# SparkFun_tDof-TMF8821.net
KiCad netlist of a schematic drawn in EAGLE
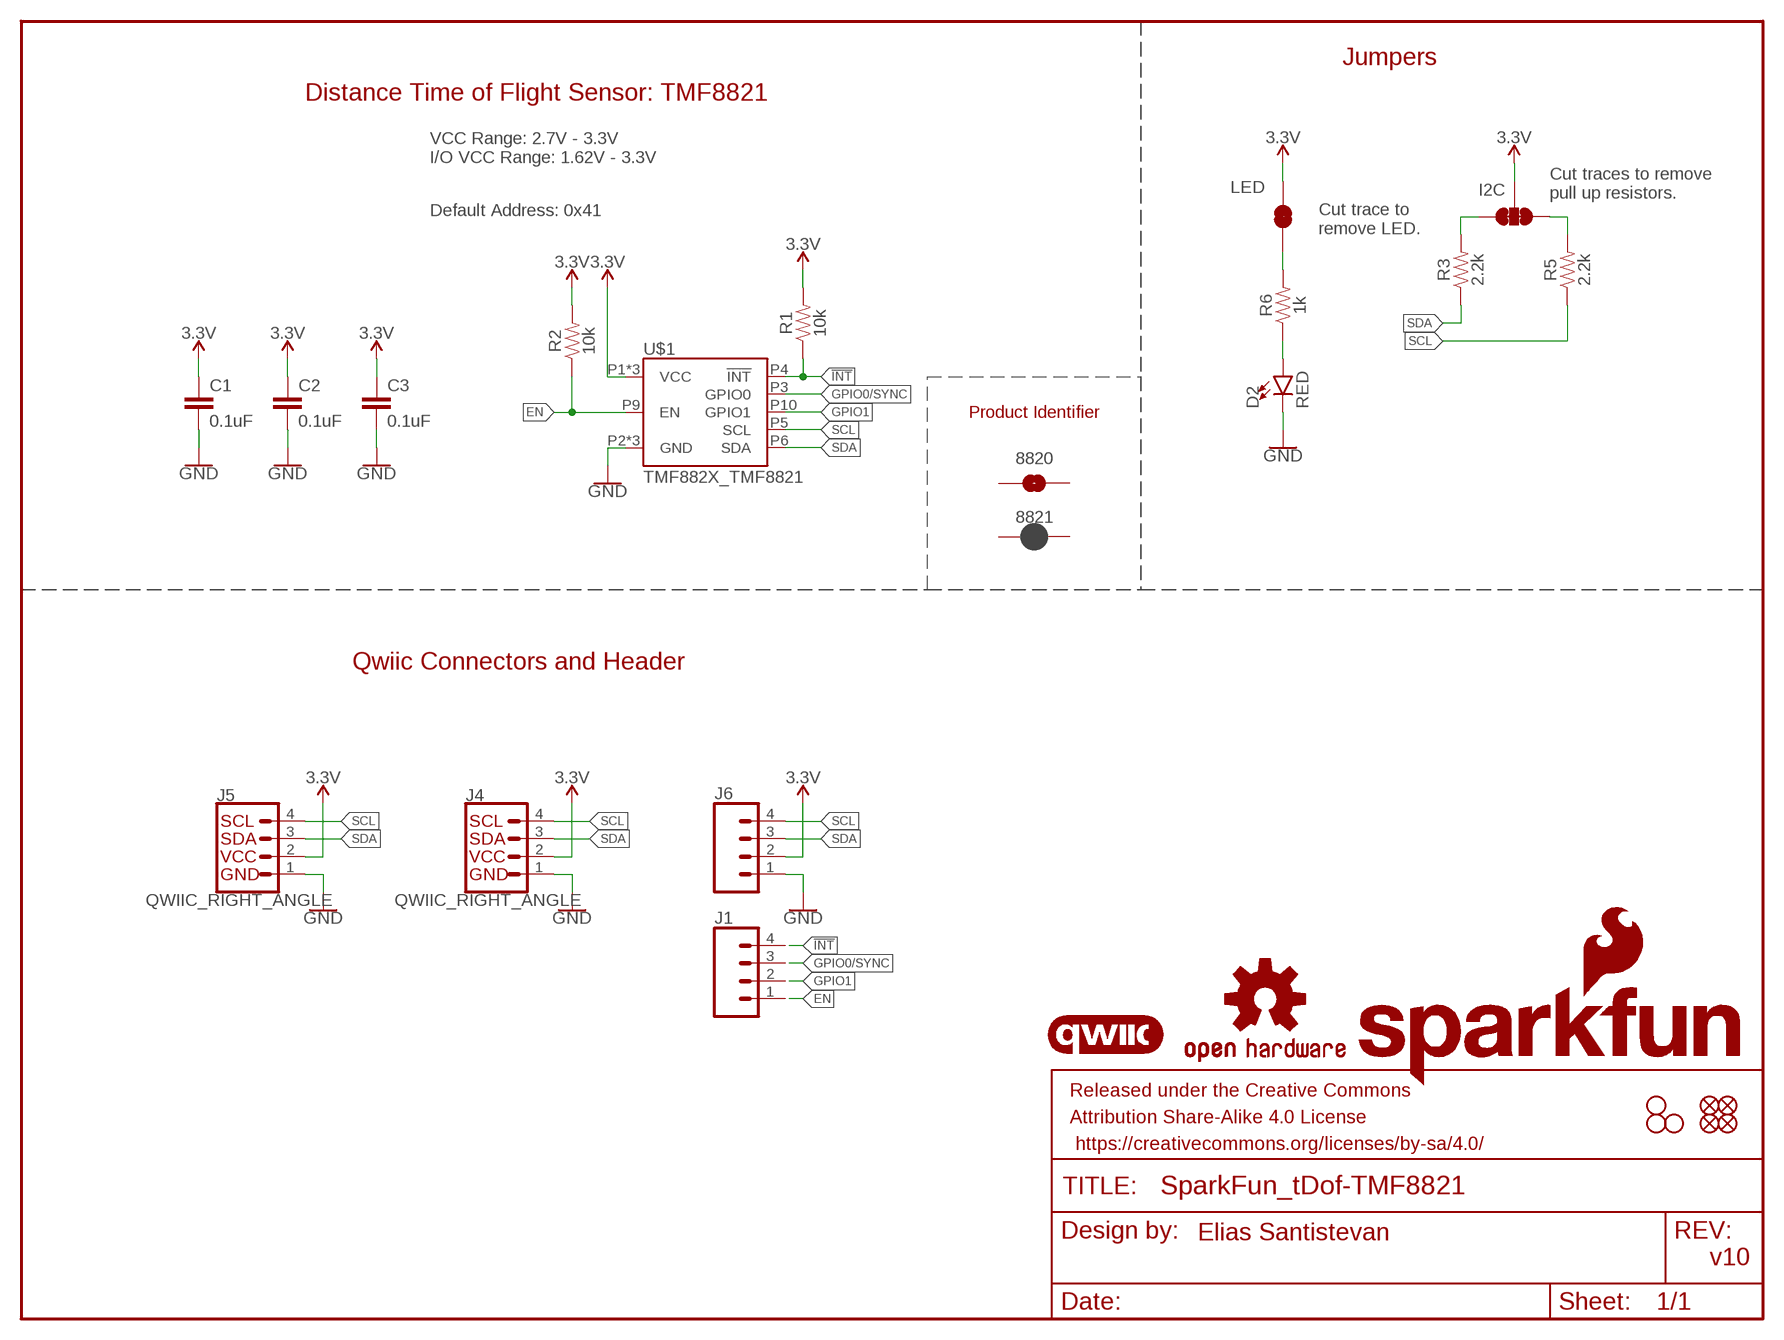
[diagram p0: schematic, sheet 1]

(export (version "E")
  (design (tool "Eeschema 10.0.6"))
  (components
    (comp (ref "8820")
      (value "JUMPER-SMT_2_NO_SILK")
      (footprint "eagle-import:SMT-JUMPER_2_NO_SILK")
      (libsource (lib "eagle-import") (part "JUMPER-SMT_2_NO_SILK"))
    )
    (comp (ref "8821")
      (value "JUMPER-SMT_2_NC_PASTE_SILK")
      (footprint "eagle-import:SMT-JUMPER_2_NC_PASTE_SILK")
      (libsource (lib "eagle-import") (part "JUMPER-SMT_2_NC_PASTE_SILK"))
    )
    (comp (ref "C1")
      (value "0.1uF")
      (footprint "eagle-import:0402-TIGHT")
      (libsource (lib "eagle-import") (part "0.1UF-0402T-6.3V-10%-X7R"))
    )
    (comp (ref "C2")
      (value "0.1uF")
      (footprint "eagle-import:0402-TIGHT")
      (libsource (lib "eagle-import") (part "0.1UF-0402T-6.3V-10%-X7R"))
    )
    (comp (ref "C3")
      (value "0.1uF")
      (footprint "eagle-import:0402-TIGHT")
      (libsource (lib "eagle-import") (part "0.1UF-0402T-6.3V-10%-X7R"))
    )
    (comp (ref "D2")
      (value "RED")
      (footprint "eagle-import:LED-0603")
      (libsource (lib "eagle-import") (part "LED-RED0603"))
    )
    (comp (ref "FD5")
      (value "FIDUCIALUFIDUCIAL")
      (footprint "eagle-import:FIDUCIAL-MICRO")
      (libsource (lib "eagle-import") (part "FIDUCIALUFIDUCIAL"))
    )
    (comp (ref "FD6")
      (value "FIDUCIALUFIDUCIAL")
      (footprint "eagle-import:FIDUCIAL-MICRO")
      (libsource (lib "eagle-import") (part "FIDUCIALUFIDUCIAL"))
    )
    (comp (ref "FD7")
      (value "FIDUCIALUFIDUCIAL")
      (footprint "eagle-import:FIDUCIAL-MICRO")
      (libsource (lib "eagle-import") (part "FIDUCIALUFIDUCIAL"))
    )
    (comp (ref "FD8")
      (value "FIDUCIALUFIDUCIAL")
      (footprint "eagle-import:FIDUCIAL-MICRO")
      (libsource (lib "eagle-import") (part "FIDUCIALUFIDUCIAL"))
    )
    (comp (ref "FRAME2")
      (value "FRAME-LETTER")
      (footprint "eagle-import:CREATIVE_COMMONS")
      (libsource (lib "eagle-import") (part "FRAME-LETTER"))
    )
    (comp (ref "H5")
      (value "STAND-OFFTIGHT")
      (footprint "eagle-import:STAND-OFF-TIGHT")
      (libsource (lib "eagle-import") (part "STAND-OFFTIGHT"))
    )
    (comp (ref "H6")
      (value "STAND-OFFTIGHT")
      (footprint "eagle-import:STAND-OFF-TIGHT")
      (libsource (lib "eagle-import") (part "STAND-OFFTIGHT"))
    )
    (comp (ref "H8")
      (value "STAND-OFFTIGHT")
      (footprint "eagle-import:STAND-OFF-TIGHT")
      (libsource (lib "eagle-import") (part "STAND-OFFTIGHT"))
    )
    (comp (ref "I2C")
      (value "I2C_PU")
      (footprint "eagle-import:SMT-JUMPER_3_2-NC_TRACE_SILK")
      (libsource (lib "eagle-import") (part "JUMPER-SMT_3_2-NC_TRACE_SILK"))
    )
    (comp (ref "J1")
      (value "CONN_041X04_NO_SILK_NO_POP")
      (footprint "eagle-import:1X04_NO_SILK")
      (libsource (lib "eagle-import") (part "CONN_041X04_NO_SILK_NO_POP"))
    )
    (comp (ref "J4")
      (value "QWIIC_RIGHT_ANGLE")
      (footprint "eagle-import:JST04_1MM_RA")
      (libsource (lib "eagle-import") (part "QWIIC_CONNECTORJS-1MM"))
    )
    (comp (ref "J5")
      (value "QWIIC_RIGHT_ANGLE")
      (footprint "eagle-import:JST04_1MM_RA")
      (libsource (lib "eagle-import") (part "QWIIC_CONNECTORJS-1MM"))
    )
    (comp (ref "J6")
      (value "CONN_041X04_NO_SILK")
      (footprint "eagle-import:1X04_NO_SILK")
      (libsource (lib "eagle-import") (part "CONN_041X04_NO_SILK"))
    )
    (comp (ref "LED")
      (value "LED")
      (footprint "eagle-import:SMT-JUMPER_2_NC_TRACE_SILK")
      (libsource (lib "eagle-import") (part "JUMPER-SMT_2_NC_TRACE_SILK"))
    )
    (comp (ref "LOGO3")
      (value "SFE_LOGO_NAME_FLAME.1_INCH")
      (footprint "eagle-import:SFE_LOGO_NAME_FLAME_.1")
      (libsource (lib "eagle-import") (part "SFE_LOGO_NAME_FLAME.1_INCH"))
    )
    (comp (ref "LOGO4")
      (value "OSHW-LOGOS")
      (footprint "eagle-import:OSHW-LOGO-S")
      (libsource (lib "eagle-import") (part "OSHW-LOGOS"))
    )
    (comp (ref "R1")
      (value "10k")
      (footprint "eagle-import:0603")
      (libsource (lib "eagle-import") (part "10KOHM-0603-1/10W-1%"))
    )
    (comp (ref "R2")
      (value "10k")
      (footprint "eagle-import:0603")
      (libsource (lib "eagle-import") (part "10KOHM-0603-1/10W-1%"))
    )
    (comp (ref "R3")
      (value "2.2k")
      (footprint "eagle-import:0603")
      (libsource (lib "eagle-import") (part "2.2KOHM-0603-1/10W-1%"))
    )
    (comp (ref "R5")
      (value "2.2k")
      (footprint "eagle-import:0603")
      (libsource (lib "eagle-import") (part "2.2KOHM-0603-1/10W-1%"))
    )
    (comp (ref "R6")
      (value "1k")
      (footprint "eagle-import:0603")
      (libsource (lib "eagle-import") (part "1KOHM-0603-1/10W-1%"))
    )
    (comp (ref "U$1")
      (value "TMF882X_TMF8821")
      (footprint "eagle-import:TMF882X")
      (libsource (lib "eagle-import") (part "TMF882X_TMF8821"))
    )
    (comp (ref "U$6")
      (value "QWIIC_LOGO_5MM")
      (footprint "eagle-import:QWIIC_5MM")
      (libsource (lib "eagle-import") (part "QWIIC_LOGO_5MM"))
    )
  )
  (nets
    (net (code "1") (name "/~{INT}") (class "Default")
      (node (ref "J1") (pin "4") (pinfunction "4_4") (pintype "passive"))
      (node (ref "R1") (pin "1") (pinfunction "1_1") (pintype "passive"))
      (node (ref "U$1") (pin "P4") (pinfunction "~{INT}_P4") (pintype "bidirectional"))
    )
    (net (code "2") (name "3.3V") (class "Default")
      (node (ref "C1") (pin "1") (pinfunction "1_1") (pintype "passive"))
      (node (ref "C2") (pin "1") (pinfunction "1_1") (pintype "passive"))
      (node (ref "C3") (pin "1") (pinfunction "1_1") (pintype "passive"))
      (node (ref "I2C") (pin "2") (pinfunction "2_2") (pintype "passive"))
      (node (ref "J4") (pin "2") (pinfunction "2_2") (pintype "power_in"))
      (node (ref "J5") (pin "2") (pinfunction "2_2") (pintype "power_in"))
      (node (ref "J6") (pin "2") (pinfunction "2_2") (pintype "passive"))
      (node (ref "LED") (pin "2") (pinfunction "2_2") (pintype "passive"))
      (node (ref "R1") (pin "2") (pinfunction "2_2") (pintype "passive"))
      (node (ref "R2") (pin "2") (pinfunction "2_2") (pintype "passive"))
      (node (ref "U$1") (pin "P1") (pinfunction "VCC_P1") (pintype "power_in"))
      (node (ref "U$1") (pin "P12") (pinfunction "VCC_P12") (pintype "power_in"))
      (node (ref "U$1") (pin "P7") (pinfunction "VCC_P7") (pintype "power_in"))
    )
    (net (code "3") (name "EN") (class "Default")
      (node (ref "J1") (pin "1") (pinfunction "1_1") (pintype "passive"))
      (node (ref "R2") (pin "1") (pinfunction "1_1") (pintype "passive"))
      (node (ref "U$1") (pin "P9") (pinfunction "EN_P9") (pintype "input"))
    )
    (net (code "4") (name "GND") (class "Default")
      (node (ref "C1") (pin "2") (pinfunction "2_2") (pintype "passive"))
      (node (ref "C2") (pin "2") (pinfunction "2_2") (pintype "passive"))
      (node (ref "C3") (pin "2") (pinfunction "2_2") (pintype "passive"))
      (node (ref "D2") (pin "C") (pinfunction "C_C") (pintype "passive"))
      (node (ref "J4") (pin "1") (pinfunction "1_1") (pintype "power_in"))
      (node (ref "J5") (pin "1") (pinfunction "1_1") (pintype "power_in"))
      (node (ref "J6") (pin "1") (pinfunction "1_1") (pintype "passive"))
      (node (ref "U$1") (pin "P11") (pinfunction "GND_P11") (pintype "power_in"))
      (node (ref "U$1") (pin "P2") (pinfunction "GND_P2") (pintype "power_in"))
      (node (ref "U$1") (pin "P8") (pinfunction "GND_P8") (pintype "power_in"))
    )
    (net (code "5") (name "GPIO0{slash}SYNC") (class "Default")
      (node (ref "J1") (pin "3") (pinfunction "3_3") (pintype "passive"))
      (node (ref "U$1") (pin "P3") (pinfunction "GPIO0_P3") (pintype "bidirectional"))
    )
    (net (code "6") (name "GPIO1") (class "Default")
      (node (ref "J1") (pin "2") (pinfunction "2_2") (pintype "passive"))
      (node (ref "U$1") (pin "P10") (pinfunction "GPIO1_P10") (pintype "bidirectional"))
    )
    (net (code "7") (name "Net-(D2-PadA)") (class "Default")
      (node (ref "D2") (pin "A") (pinfunction "A_A") (pintype "passive"))
      (node (ref "R6") (pin "1") (pinfunction "1_1") (pintype "passive"))
    )
    (net (code "8") (name "Net-(I2C-Pad1)") (class "Default")
      (node (ref "I2C") (pin "1") (pinfunction "1_1") (pintype "passive"))
      (node (ref "R5") (pin "2") (pinfunction "2_2") (pintype "passive"))
    )
    (net (code "9") (name "Net-(I2C-Pad3)") (class "Default")
      (node (ref "I2C") (pin "3") (pinfunction "3_3") (pintype "passive"))
      (node (ref "R3") (pin "2") (pinfunction "2_2") (pintype "passive"))
    )
    (net (code "10") (name "Net-(LED-Pad1)") (class "Default")
      (node (ref "LED") (pin "1") (pinfunction "1_1") (pintype "passive"))
      (node (ref "R6") (pin "2") (pinfunction "2_2") (pintype "passive"))
    )
    (net (code "11") (name "SCL") (class "Default")
      (node (ref "J4") (pin "4") (pinfunction "4_4") (pintype "passive"))
      (node (ref "J5") (pin "4") (pinfunction "4_4") (pintype "passive"))
      (node (ref "J6") (pin "4") (pinfunction "4_4") (pintype "passive"))
      (node (ref "R5") (pin "1") (pinfunction "1_1") (pintype "passive"))
      (node (ref "U$1") (pin "P5") (pinfunction "SCL_P5") (pintype "bidirectional"))
    )
    (net (code "12") (name "SDA") (class "Default")
      (node (ref "J4") (pin "3") (pinfunction "3_3") (pintype "passive"))
      (node (ref "J5") (pin "3") (pinfunction "3_3") (pintype "passive"))
      (node (ref "J6") (pin "3") (pinfunction "3_3") (pintype "passive"))
      (node (ref "R3") (pin "1") (pinfunction "1_1") (pintype "passive"))
      (node (ref "U$1") (pin "P6") (pinfunction "SDA_P6") (pintype "bidirectional"))
    )
    (net (code "13") (name "unconnected-(8820-Pad1)") (class "Default")
      (node (ref "8820") (pin "1") (pinfunction "1_1") (pintype "passive"))
    )
    (net (code "14") (name "unconnected-(8820-Pad2)") (class "Default")
      (node (ref "8820") (pin "2") (pinfunction "2_2") (pintype "passive"))
    )
    (net (code "15") (name "unconnected-(8821-Pad1)") (class "Default")
      (node (ref "8821") (pin "1") (pinfunction "1_1") (pintype "passive"))
    )
    (net (code "16") (name "unconnected-(8821-Pad2)") (class "Default")
      (node (ref "8821") (pin "2") (pinfunction "2_2") (pintype "passive"))
    )
  )
)
